# PSU.net
KiCad netlist of a schematic drawn in Altium Designer
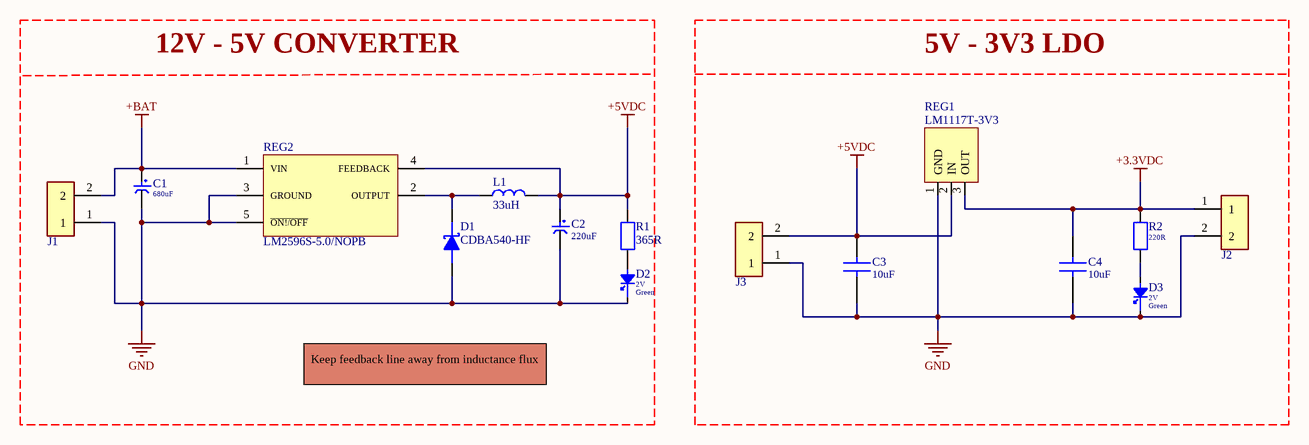
[diagram p0: PSU.SchDoc]

(export (version "E")
  (design (tool "Eeschema 10.0.6"))
  (components
    (comp (ref "C1")
      (value "EEU-FR1V681")
      (footprint "CAP ALI 10MM RADIAL")
      (description "CAP ALUM 680UF 20% 35V RADIAL")
      (fields
        (field (name "MANUFACTURER") "Panasonic")
        (field (name "TOLERANCE") "20%")
        (field (name "CAPACITANCE") "680uF")
      )
      (libsource (lib "Schlib1") (part "CAP ALUM 680UF 35V  RADIAL"))
    )
    (comp (ref "C2")
      (value "ESH227M016AE3AA")
      (footprint "CAP ALI 6.30MM RADIAL")
      (description "Capacitor;  Al Electrolytic;  Cap 220 uF;  Tol 20%;  Vol-Rtg 16 VDC;  Radial;  6x11 mm")
      (fields
        (field (name "MANUFACTURER") "KEMET")
        (field (name "TOLERANCE") "20%")
        (field (name "CAPACITANCE") "220uF")
      )
      (libsource (lib "Schlib1") (part "CAP ALUM 220UF 16V  RADIAL_1"))
    )
    (comp (ref "C3")
      (value "GRM21BR61E106MA73L")
      (footprint "CAP CER 0805")
      (fields
        (field (name "MANUFACTURER") "Murata")
        (field (name "TOLERANCE") "20%")
        (field (name "CAPACITANCE") "10uF")
      )
      (libsource (lib "Schlib1") (part "CAP CER 10UF 25V 0805"))
    )
    (comp (ref "C4")
      (value "GRM21BR61E106MA73L")
      (footprint "CAP CER 0805")
      (fields
        (field (name "MANUFACTURER") "Murata")
        (field (name "TOLERANCE") "20%")
        (field (name "CAPACITANCE") "10uF")
      )
      (libsource (lib "Schlib1") (part "CAP CER 10UF 25V 0805"))
    )
    (comp (ref "D1")
      (value "CDBA540-HF")
      (footprint "DO-214AC")
      (description "DIODE SCHOTTKY 40V 5A DO214AC")
      (fields (field (name "MANUFACTURER") "Comchip"))
      (libsource (lib "Schlib1") (part "CDBA540-HF"))
    )
    (comp (ref "D2")
      (value "150060VS75000")
      (footprint "LED GR 0603")
      (description "CRCW Thick Film Commodity Chip Resistor 0603 Size 5.1K Ohm 1% 0.1 W 100 ppm/K 2-Pin SMD Paper T/R")
      (fields
        (field (name "MANUFACTURER") "Wurth Electronics")
        (field (name "TOLERANCE") "1%")
        (field (name "FORWARD VOLTAGE") "2V")
        (field (name "COLOR") "Green")
      )
      (libsource (lib "Schlib1") (part "LED GR 0603"))
    )
    (comp (ref "D3")
      (value "150060VS75000")
      (footprint "LED GR 0603")
      (description "CRCW Thick Film Commodity Chip Resistor 0603 Size 5.1K Ohm 1% 0.1 W 100 ppm/K 2-Pin SMD Paper T/R")
      (fields
        (field (name "MANUFACTURER") "Wurth Electronics")
        (field (name "TOLERANCE") "1%")
        (field (name "FORWARD VOLTAGE") "2V")
        (field (name "COLOR") "Green")
      )
      (libsource (lib "Schlib1") (part "LED GR 0603"))
    )
    (comp (ref "J1")
      (value "2X1 KLEMENS")
      (footprint "2X1 CONNECTOR")
      (description "Conn PC Terminal Block 2 POS 5mm Solder ST Thru-Hole 17.5A")
      (fields
        (field (name "MANUFACTURER") "Phoenix Contact")
        (field (name "MANUFACTURER PART NUMBER") "1935161")
      )
      (libsource (lib "Schlib1") (part "2X1 KLEMENS"))
    )
    (comp (ref "J2")
      (value "2X1 KLEMENS")
      (footprint "2X1 CONNECTOR")
      (description "Conn PC Terminal Block 2 POS 5mm Solder ST Thru-Hole 17.5A")
      (fields
        (field (name "MANUFACTURER") "Phoenix Contact")
        (field (name "MANUFACTURER PART NUMBER") "1935161")
      )
      (libsource (lib "") (part "2X1 KLEMENS_1"))
    )
    (comp (ref "J3")
      (value "2X1 KLEMENS")
      (footprint "2X1 CONNECTOR")
      (description "Conn PC Terminal Block 2 POS 5mm Solder ST Thru-Hole 17.5A")
      (fields
        (field (name "MANUFACTURER") "Phoenix Contact")
        (field (name "MANUFACTURER PART NUMBER") "1935161")
      )
      (libsource (lib "Schlib1") (part "2X1 KLEMENS"))
    )
    (comp (ref "L1")
      (value "SRR1280-330M")
      (footprint "SRR1280-330M")
      (description "33uH 20% 100KHz Ind Power Shielded Wirewound  28Q-Factor Ferrite 3.5A T/R")
      (fields
        (field (name "MANUFACTURER") "Bourns")
        (field (name "TOLERANCE") "20%")
        (field (name "INDUCTANCE") "33uH")
      )
      (libsource (lib "Schlib1") (part "IND 33uH"))
    )
    (comp (ref "R1")
      (value "RC0805FR-07365RL")
      (footprint "RES 0805")
      (description "RES SMD 365 OHM 1% 1/8W 0805")
      (fields
        (field (name "MANUFACTURER") "Yageo")
        (field (name "TOLERANCE") "1%")
        (field (name "RESISTANCE") "365R")
      )
      (libsource (lib "Schlib1") (part "RES 365R 0805"))
    )
    (comp (ref "R2")
      (value "220R")
      (footprint "RES 0805")
      (description "Res Thick Film 0805 220 Ohm 5% 0.125W(1/8W) ±100ppm/C Pad SMD Automotive T/R")
      (fields
        (field (name "MANUFACTURER") "TE Connectivity")
        (field (name "MANUFACTURER PART NUMBER") "CRGCQ0805J220R")
      )
      (libsource (lib "Schlib1") (part "RES 220R 0805"))
    )
    (comp (ref "REG1")
      (value "LM1117T-3V3")
      (footprint "LM1117-3V3")
      (description "800-mA 15-V linear voltage regulator 3-TO-220 0 to 125")
      (fields
        (field (name "MANUFACTURER") "TI National Semiconductor")
        (field (name "MANUFACTURER PART NUMBER") "LM1117T-3.3/NOPB")
      )
      (libsource (lib "Schlib1") (part "LM1117T-3V3"))
    )
    (comp (ref "REG2")
      (value "LM2596S-5.0/NOPB")
      (footprint "LM2596S-5.0/NOPB")
      (description "Conv DC-DC 4.5V to 40V Inv/Step Down Single-Out 5V 3A 6-Pin(5+Tab) TO-263 Tube")
      (fields (field (name "MANUFACTURER") "TI National Semiconductor"))
      (libsource (lib "Schlib1") (part "LM2596S-5.0/NOPB"))
    )
  )
  (nets
    (net (code "1") (name "+3.3VDC") (class "Default")
      (node (ref "C4") (pin "2") (pinfunction "2_2") (pintype "passive"))
      (node (ref "J2") (pin "1") (pinfunction "1_1") (pintype "passive"))
      (node (ref "R2") (pin "2") (pinfunction "2_2") (pintype "passive"))
      (node (ref "REG1") (pin "3") (pinfunction "OUT_3") (pintype "passive"))
    )
    (net (code "2") (name "+5VDC") (class "Default")
      (node (ref "C2") (pin "1") (pinfunction "1_1") (pintype "passive"))
      (node (ref "C3") (pin "2") (pinfunction "2_2") (pintype "passive"))
      (node (ref "J3") (pin "2") (pinfunction "2_2") (pintype "passive"))
      (node (ref "L1") (pin "2") (pinfunction "2_2") (pintype "passive"))
      (node (ref "R1") (pin "2") (pinfunction "2_2") (pintype "passive"))
      (node (ref "REG1") (pin "2") (pinfunction "IN_2") (pintype "passive"))
      (node (ref "REG2") (pin "4") (pinfunction "FEEDBACK_4") (pintype "power_in"))
    )
    (net (code "3") (name "+BAT") (class "Default")
      (node (ref "C1") (pin "1") (pinfunction "1_1") (pintype "passive"))
      (node (ref "J1") (pin "2") (pinfunction "2_2") (pintype "passive"))
      (node (ref "REG2") (pin "1") (pinfunction "VIN_1") (pintype "power_in"))
    )
    (net (code "4") (name "GND") (class "Default")
      (node (ref "C1") (pin "2") (pinfunction "2_2") (pintype "passive"))
      (node (ref "C2") (pin "2") (pinfunction "2_2") (pintype "passive"))
      (node (ref "C3") (pin "1") (pinfunction "1_1") (pintype "passive"))
      (node (ref "C4") (pin "1") (pinfunction "1_1") (pintype "passive"))
      (node (ref "D1") (pin "A") (pinfunction "A_A") (pintype "passive"))
      (node (ref "D2") (pin "1") (pinfunction "1_1") (pintype "passive"))
      (node (ref "D3") (pin "1") (pinfunction "1_1") (pintype "passive"))
      (node (ref "J1") (pin "1") (pinfunction "1_1") (pintype "passive"))
      (node (ref "J2") (pin "2") (pinfunction "2_2") (pintype "passive"))
      (node (ref "J3") (pin "1") (pinfunction "1_1") (pintype "passive"))
      (node (ref "REG1") (pin "1") (pinfunction "GND_1") (pintype "passive"))
      (node (ref "REG2") (pin "3") (pinfunction "GROUND_3") (pintype "power_in"))
      (node (ref "REG2") (pin "5") (pinfunction "~{ON!/OFF}_5") (pintype "power_in"))
    )
    (net (code "5") (name "Net-(D2-Pad2)") (class "Default")
      (node (ref "D2") (pin "2") (pinfunction "2_2") (pintype "passive"))
      (node (ref "R1") (pin "1") (pinfunction "1_1") (pintype "passive"))
    )
    (net (code "6") (name "Net-(D3-Pad2)") (class "Default")
      (node (ref "D3") (pin "2") (pinfunction "2_2") (pintype "passive"))
      (node (ref "R2") (pin "1") (pinfunction "1_1") (pintype "passive"))
    )
    (net (code "7") (name "Net-(REG2-OUTPUT)") (class "Default")
      (node (ref "D1") (pin "C") (pinfunction "C_C") (pintype "passive"))
      (node (ref "L1") (pin "1") (pinfunction "1_1") (pintype "passive"))
      (node (ref "REG2") (pin "2") (pinfunction "OUTPUT_2") (pintype "power_in"))
    )
  )
)
